# PTSymmetryControllerSchematic.net
KiCad netlist of a schematic drawn in EAGLE
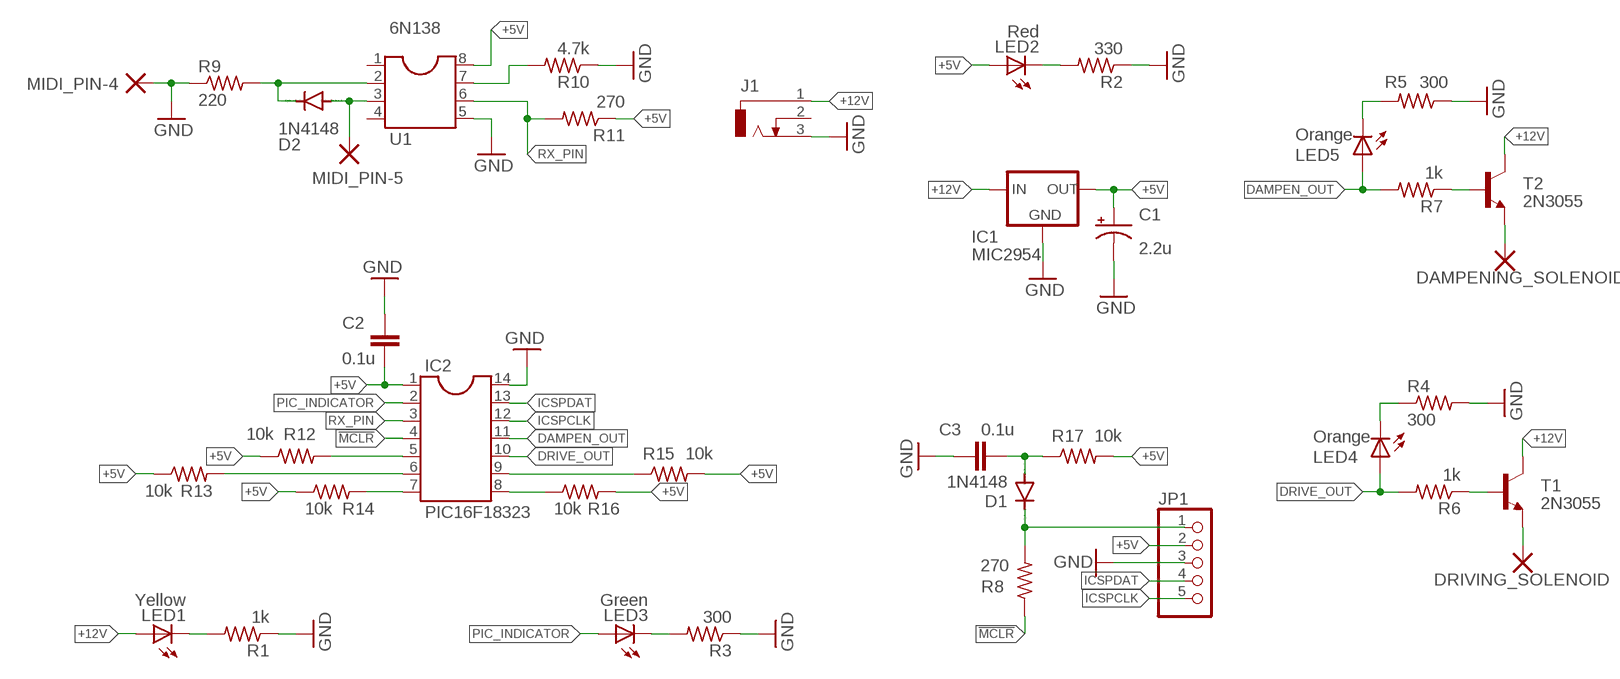
[diagram p0: schematic, sheet 1]

(export (version "E")
  (design (tool "Eeschema 10.0.6"))
  (components
    (comp (ref "6N138")
      (value "U1")
      (footprint "eagle-import:SOCKET-08")
      (libsource (lib "eagle-import") (part "DIL8S"))
    )
    (comp (ref "C1")
      (value "2.2u")
      (footprint "eagle-import:E2,5-6")
      (libsource (lib "eagle-import") (part "CPOL-USE2.5-6"))
    )
    (comp (ref "C2")
      (value "0.1u")
      (footprint "eagle-import:C5B2.5")
      (libsource (lib "eagle-import") (part "C5/2.5"))
    )
    (comp (ref "C3")
      (value "0.1u")
      (footprint "eagle-import:C5B2.5")
      (libsource (lib "eagle-import") (part "C5/2.5"))
    )
    (comp (ref "D1")
      (value "1N4148")
      (footprint "eagle-import:DO35-10")
      (libsource (lib "eagle-import") (part "1N4148DO35-10"))
    )
    (comp (ref "D2")
      (value "1N4148")
      (footprint "eagle-import:DO35-10")
      (libsource (lib "eagle-import") (part "1N4148DO35-10"))
    )
    (comp (ref "DAMPENING_SOLENOID")
      (value "DOUBLE_THROUGH_HOLE_PAD")
      (footprint "eagle-import:DOUBLE_THROUGH_HOLE_PAD")
      (libsource (lib "eagle-import") (part "DOUBLE_THROUGH_HOLE_PAD"))
    )
    (comp (ref "DRIVING_SOLENOID")
      (value "DOUBLE_THROUGH_HOLE_PAD")
      (footprint "eagle-import:DOUBLE_THROUGH_HOLE_PAD")
      (libsource (lib "eagle-import") (part "DOUBLE_THROUGH_HOLE_PAD"))
    )
    (comp (ref "IC1")
      (value "MIC2954")
      (footprint "eagle-import:78XXL")
      (libsource (lib "eagle-import") (part "78XXL"))
    )
    (comp (ref "IC2")
      (value "PIC16F18323")
      (footprint "eagle-import:SOCKET-14")
      (libsource (lib "eagle-import") (part "DIL14S"))
    )
    (comp (ref "J1")
      (value "DCJ0303")
      (footprint "eagle-import:DCJ0303")
      (libsource (lib "eagle-import") (part "DCJ0303"))
    )
    (comp (ref "JP1")
      (value "1x5x2mm-pinheader")
      (footprint "eagle-import:1X05")
      (libsource (lib "eagle-import") (part "PINHD-1X5"))
    )
    (comp (ref "LED1")
      (value "Yellow")
      (footprint "eagle-import:LED5MM")
      (libsource (lib "eagle-import") (part "LED5MM"))
    )
    (comp (ref "LED2")
      (value "Red")
      (footprint "eagle-import:LED5MM")
      (libsource (lib "eagle-import") (part "LED5MM"))
    )
    (comp (ref "LED3")
      (value "Green")
      (footprint "eagle-import:LED5MM")
      (libsource (lib "eagle-import") (part "LED5MM"))
    )
    (comp (ref "LED4")
      (value "Orange")
      (footprint "eagle-import:LED5MM")
      (libsource (lib "eagle-import") (part "LED5MM"))
    )
    (comp (ref "LED5")
      (value "Orange")
      (footprint "eagle-import:LED5MM")
      (libsource (lib "eagle-import") (part "LED5MM"))
    )
    (comp (ref "MIDI_PIN-4")
      (value "DOUBLE_THROUGH_HOLE_PAD")
      (footprint "eagle-import:DOUBLE_THROUGH_HOLE_PAD")
      (libsource (lib "eagle-import") (part "DOUBLE_THROUGH_HOLE_PAD"))
    )
    (comp (ref "MIDI_PIN-5")
      (value "DOUBLE_THROUGH_HOLE_PAD")
      (footprint "eagle-import:DOUBLE_THROUGH_HOLE_PAD")
      (libsource (lib "eagle-import") (part "DOUBLE_THROUGH_HOLE_PAD"))
    )
    (comp (ref "R1")
      (value "1k")
      (footprint "eagle-import:0207_10")
      (libsource (lib "eagle-import") (part "R-US_0207/10"))
    )
    (comp (ref "R2")
      (value "330")
      (footprint "eagle-import:0207_10")
      (libsource (lib "eagle-import") (part "R-US_0207/10"))
    )
    (comp (ref "R3")
      (value "300")
      (footprint "eagle-import:0207_10")
      (libsource (lib "eagle-import") (part "R-US_0207/10"))
    )
    (comp (ref "R4")
      (value "300")
      (footprint "eagle-import:0207_10")
      (libsource (lib "eagle-import") (part "R-US_0207/10"))
    )
    (comp (ref "R5")
      (value "300")
      (footprint "eagle-import:0207_10")
      (libsource (lib "eagle-import") (part "R-US_0207/10"))
    )
    (comp (ref "R6")
      (value "1k")
      (footprint "eagle-import:0207_10")
      (libsource (lib "eagle-import") (part "R-US_0207/10"))
    )
    (comp (ref "R7")
      (value "1k")
      (footprint "eagle-import:0207_10")
      (libsource (lib "eagle-import") (part "R-US_0207/10"))
    )
    (comp (ref "R8")
      (value "270")
      (footprint "eagle-import:0207_10")
      (libsource (lib "eagle-import") (part "R-US_0207/10"))
    )
    (comp (ref "R9")
      (value "220")
      (footprint "eagle-import:0207_12")
      (libsource (lib "eagle-import") (part "resistor_348_R-US_0207/12"))
    )
    (comp (ref "R10")
      (value "4.7k")
      (footprint "eagle-import:0207_12")
      (libsource (lib "eagle-import") (part "resistor_348_R-US_0207/12"))
    )
    (comp (ref "R11")
      (value "270")
      (footprint "eagle-import:0207_12")
      (libsource (lib "eagle-import") (part "resistor_348_R-US_0207/12"))
    )
    (comp (ref "R12")
      (value "10k")
      (footprint "eagle-import:0207_10")
      (libsource (lib "eagle-import") (part "R-US_0207/10"))
    )
    (comp (ref "R13")
      (value "10k")
      (footprint "eagle-import:0207_10")
      (libsource (lib "eagle-import") (part "R-US_0207/10"))
    )
    (comp (ref "R14")
      (value "10k")
      (footprint "eagle-import:0207_10")
      (libsource (lib "eagle-import") (part "R-US_0207/10"))
    )
    (comp (ref "R15")
      (value "10k")
      (footprint "eagle-import:0207_10")
      (libsource (lib "eagle-import") (part "R-US_0207/10"))
    )
    (comp (ref "R16")
      (value "10k")
      (footprint "eagle-import:0207_10")
      (libsource (lib "eagle-import") (part "R-US_0207/10"))
    )
    (comp (ref "R17")
      (value "10k")
      (footprint "eagle-import:0207_10")
      (libsource (lib "eagle-import") (part "R-US_0207/10"))
    )
    (comp (ref "T1")
      (value "2N3055")
      (footprint "eagle-import:TO3")
      (libsource (lib "eagle-import") (part "2N3055"))
    )
    (comp (ref "T2")
      (value "2N3055")
      (footprint "eagle-import:TO3")
      (libsource (lib "eagle-import") (part "2N3055"))
    )
  )
  (nets
    (net (code "1") (name "+5V") (class "Default")
      (node (ref "6N138") (pin "8") (pinfunction "8_8") (pintype "passive"))
      (node (ref "C1") (pin "+") (pinfunction "+_+") (pintype "passive"))
      (node (ref "C2") (pin "2") (pinfunction "2_2") (pintype "passive"))
      (node (ref "IC1") (pin "OUT") (pinfunction "OUT_OUT") (pintype "passive"))
      (node (ref "IC2") (pin "1") (pinfunction "1_1") (pintype "passive"))
      (node (ref "JP1") (pin "2") (pinfunction "2_2") (pintype "passive"))
      (node (ref "LED2") (pin "A") (pinfunction "A_A") (pintype "passive"))
      (node (ref "R11") (pin "1") (pinfunction "1_1") (pintype "passive"))
      (node (ref "R12") (pin "1") (pinfunction "1_1") (pintype "passive"))
      (node (ref "R13") (pin "1") (pinfunction "1_1") (pintype "passive"))
      (node (ref "R14") (pin "1") (pinfunction "1_1") (pintype "passive"))
      (node (ref "R15") (pin "2") (pinfunction "2_2") (pintype "passive"))
      (node (ref "R16") (pin "2") (pinfunction "2_2") (pintype "passive"))
      (node (ref "R17") (pin "2") (pinfunction "2_2") (pintype "passive"))
    )
    (net (code "2") (name "+12V") (class "Default")
      (node (ref "IC1") (pin "IN") (pinfunction "IN_IN") (pintype "input"))
      (node (ref "J1") (pin "1") (pinfunction "1_1") (pintype "passive"))
      (node (ref "LED1") (pin "A") (pinfunction "A_A") (pintype "passive"))
      (node (ref "T1") (pin "C") (pinfunction "C_C") (pintype "passive"))
      (node (ref "T1") (pin "C/") (pinfunction "C_C/") (pintype "passive"))
      (node (ref "T2") (pin "C") (pinfunction "C_C") (pintype "passive"))
      (node (ref "T2") (pin "C/") (pinfunction "C_C/") (pintype "passive"))
    )
    (net (code "3") (name "/~{MCLR}") (class "Default")
      (node (ref "IC2") (pin "4") (pinfunction "4_4") (pintype "passive"))
      (node (ref "R8") (pin "1") (pinfunction "1_1") (pintype "passive"))
    )
    (net (code "4") (name "DAMPEN_OUT") (class "Default")
      (node (ref "IC2") (pin "11") (pinfunction "11_11") (pintype "passive"))
      (node (ref "LED5") (pin "A") (pinfunction "A_A") (pintype "passive"))
      (node (ref "R7") (pin "2") (pinfunction "2_2") (pintype "passive"))
    )
    (net (code "5") (name "DRIVE_OUT") (class "Default")
      (node (ref "IC2") (pin "10") (pinfunction "10_10") (pintype "passive"))
      (node (ref "LED4") (pin "A") (pinfunction "A_A") (pintype "passive"))
      (node (ref "R6") (pin "2") (pinfunction "2_2") (pintype "passive"))
    )
    (net (code "6") (name "GND") (class "Default")
      (node (ref "6N138") (pin "5") (pinfunction "5_5") (pintype "passive"))
      (node (ref "C1") (pin "-") (pinfunction "-_-") (pintype "passive"))
      (node (ref "C2") (pin "1") (pinfunction "1_1") (pintype "passive"))
      (node (ref "C3") (pin "1") (pinfunction "1_1") (pintype "passive"))
      (node (ref "IC1") (pin "GND") (pinfunction "GND_GND") (pintype "input"))
      (node (ref "IC2") (pin "14") (pinfunction "14_14") (pintype "passive"))
      (node (ref "J1") (pin "3") (pinfunction "3_3") (pintype "passive"))
      (node (ref "JP1") (pin "3") (pinfunction "3_3") (pintype "passive"))
      (node (ref "MIDI_PIN-4") (pin "P$1") (pinfunction "P$1_P$1") (pintype "bidirectional"))
      (node (ref "R1") (pin "1") (pinfunction "1_1") (pintype "passive"))
      (node (ref "R10") (pin "1") (pinfunction "1_1") (pintype "passive"))
      (node (ref "R2") (pin "1") (pinfunction "1_1") (pintype "passive"))
      (node (ref "R3") (pin "1") (pinfunction "1_1") (pintype "passive"))
      (node (ref "R4") (pin "2") (pinfunction "2_2") (pintype "passive"))
      (node (ref "R5") (pin "1") (pinfunction "1_1") (pintype "passive"))
      (node (ref "R9") (pin "1") (pinfunction "1_1") (pintype "passive"))
    )
    (net (code "7") (name "ICSPCLK") (class "Default")
      (node (ref "IC2") (pin "12") (pinfunction "12_12") (pintype "passive"))
      (node (ref "JP1") (pin "5") (pinfunction "5_5") (pintype "passive"))
    )
    (net (code "8") (name "ICSPDAT") (class "Default")
      (node (ref "IC2") (pin "13") (pinfunction "13_13") (pintype "passive"))
      (node (ref "JP1") (pin "4") (pinfunction "4_4") (pintype "passive"))
    )
    (net (code "9") (name "Net-(6N138-Pad2)") (class "Default")
      (node (ref "6N138") (pin "2") (pinfunction "2_2") (pintype "passive"))
      (node (ref "D2") (pin "C") (pinfunction "C_C") (pintype "passive"))
      (node (ref "R9") (pin "2") (pinfunction "2_2") (pintype "passive"))
    )
    (net (code "10") (name "Net-(6N138-Pad3)") (class "Default")
      (node (ref "6N138") (pin "3") (pinfunction "3_3") (pintype "passive"))
      (node (ref "D2") (pin "A") (pinfunction "A_A") (pintype "passive"))
      (node (ref "MIDI_PIN-5") (pin "P$1") (pinfunction "P$1_P$1") (pintype "bidirectional"))
    )
    (net (code "11") (name "Net-(6N138-Pad7)") (class "Default")
      (node (ref "6N138") (pin "7") (pinfunction "7_7") (pintype "passive"))
      (node (ref "R10") (pin "2") (pinfunction "2_2") (pintype "passive"))
    )
    (net (code "12") (name "Net-(C3-Pad2)") (class "Default")
      (node (ref "C3") (pin "2") (pinfunction "2_2") (pintype "passive"))
      (node (ref "D1") (pin "A") (pinfunction "A_A") (pintype "passive"))
      (node (ref "R17") (pin "1") (pinfunction "1_1") (pintype "passive"))
    )
    (net (code "13") (name "Net-(D1-PadC)") (class "Default")
      (node (ref "D1") (pin "C") (pinfunction "C_C") (pintype "passive"))
      (node (ref "JP1") (pin "1") (pinfunction "1_1") (pintype "passive"))
      (node (ref "R8") (pin "2") (pinfunction "2_2") (pintype "passive"))
    )
    (net (code "14") (name "Net-(DAMPENING_SOLENOID-PadP$1)") (class "Default")
      (node (ref "DAMPENING_SOLENOID") (pin "P$1") (pinfunction "P$1_P$1") (pintype "bidirectional"))
      (node (ref "T2") (pin "E") (pinfunction "E_E") (pintype "passive"))
    )
    (net (code "15") (name "Net-(DRIVING_SOLENOID-PadP$1)") (class "Default")
      (node (ref "DRIVING_SOLENOID") (pin "P$1") (pinfunction "P$1_P$1") (pintype "bidirectional"))
      (node (ref "T1") (pin "E") (pinfunction "E_E") (pintype "passive"))
    )
    (net (code "16") (name "Net-(IC2-Pad5)") (class "Default")
      (node (ref "IC2") (pin "5") (pinfunction "5_5") (pintype "passive"))
      (node (ref "R12") (pin "2") (pinfunction "2_2") (pintype "passive"))
    )
    (net (code "17") (name "Net-(IC2-Pad6)") (class "Default")
      (node (ref "IC2") (pin "6") (pinfunction "6_6") (pintype "passive"))
      (node (ref "R13") (pin "2") (pinfunction "2_2") (pintype "passive"))
    )
    (net (code "18") (name "Net-(IC2-Pad7)") (class "Default")
      (node (ref "IC2") (pin "7") (pinfunction "7_7") (pintype "passive"))
      (node (ref "R14") (pin "2") (pinfunction "2_2") (pintype "passive"))
    )
    (net (code "19") (name "Net-(IC2-Pad8)") (class "Default")
      (node (ref "IC2") (pin "8") (pinfunction "8_8") (pintype "passive"))
      (node (ref "R16") (pin "1") (pinfunction "1_1") (pintype "passive"))
    )
    (net (code "20") (name "Net-(IC2-Pad9)") (class "Default")
      (node (ref "IC2") (pin "9") (pinfunction "9_9") (pintype "passive"))
      (node (ref "R15") (pin "1") (pinfunction "1_1") (pintype "passive"))
    )
    (net (code "21") (name "Net-(LED1-C)") (class "Default")
      (node (ref "LED1") (pin "K") (pinfunction "C_K") (pintype "passive"))
      (node (ref "R1") (pin "2") (pinfunction "2_2") (pintype "passive"))
    )
    (net (code "22") (name "Net-(LED2-C)") (class "Default")
      (node (ref "LED2") (pin "K") (pinfunction "C_K") (pintype "passive"))
      (node (ref "R2") (pin "2") (pinfunction "2_2") (pintype "passive"))
    )
    (net (code "23") (name "Net-(LED3-C)") (class "Default")
      (node (ref "LED3") (pin "K") (pinfunction "C_K") (pintype "passive"))
      (node (ref "R3") (pin "2") (pinfunction "2_2") (pintype "passive"))
    )
    (net (code "24") (name "Net-(LED4-C)") (class "Default")
      (node (ref "LED4") (pin "K") (pinfunction "C_K") (pintype "passive"))
      (node (ref "R4") (pin "1") (pinfunction "1_1") (pintype "passive"))
    )
    (net (code "25") (name "Net-(LED5-C)") (class "Default")
      (node (ref "LED5") (pin "K") (pinfunction "C_K") (pintype "passive"))
      (node (ref "R5") (pin "2") (pinfunction "2_2") (pintype "passive"))
    )
    (net (code "26") (name "Net-(R6-Pad1)") (class "Default")
      (node (ref "R6") (pin "1") (pinfunction "1_1") (pintype "passive"))
      (node (ref "T1") (pin "B") (pinfunction "B_B") (pintype "passive"))
    )
    (net (code "27") (name "Net-(R7-Pad1)") (class "Default")
      (node (ref "R7") (pin "1") (pinfunction "1_1") (pintype "passive"))
      (node (ref "T2") (pin "B") (pinfunction "B_B") (pintype "passive"))
    )
    (net (code "28") (name "PIC_INDICATOR") (class "Default")
      (node (ref "IC2") (pin "2") (pinfunction "2_2") (pintype "passive"))
      (node (ref "LED3") (pin "A") (pinfunction "A_A") (pintype "passive"))
    )
    (net (code "29") (name "RX_PIN") (class "Default")
      (node (ref "6N138") (pin "6") (pinfunction "6_6") (pintype "passive"))
      (node (ref "IC2") (pin "3") (pinfunction "3_3") (pintype "passive"))
      (node (ref "R11") (pin "2") (pinfunction "2_2") (pintype "passive"))
    )
    (net (code "30") (name "unconnected-(6N138-Pad1)") (class "Default")
      (node (ref "6N138") (pin "1") (pinfunction "1_1") (pintype "passive"))
    )
    (net (code "31") (name "unconnected-(6N138-Pad4)") (class "Default")
      (node (ref "6N138") (pin "4") (pinfunction "4_4") (pintype "passive"))
    )
    (net (code "32") (name "unconnected-(J1-Pad2)") (class "Default")
      (node (ref "J1") (pin "2") (pinfunction "2_2") (pintype "passive"))
    )
  )
)
